# ASD2411.net
KiCad netlist of a schematic drawn in EAGLE
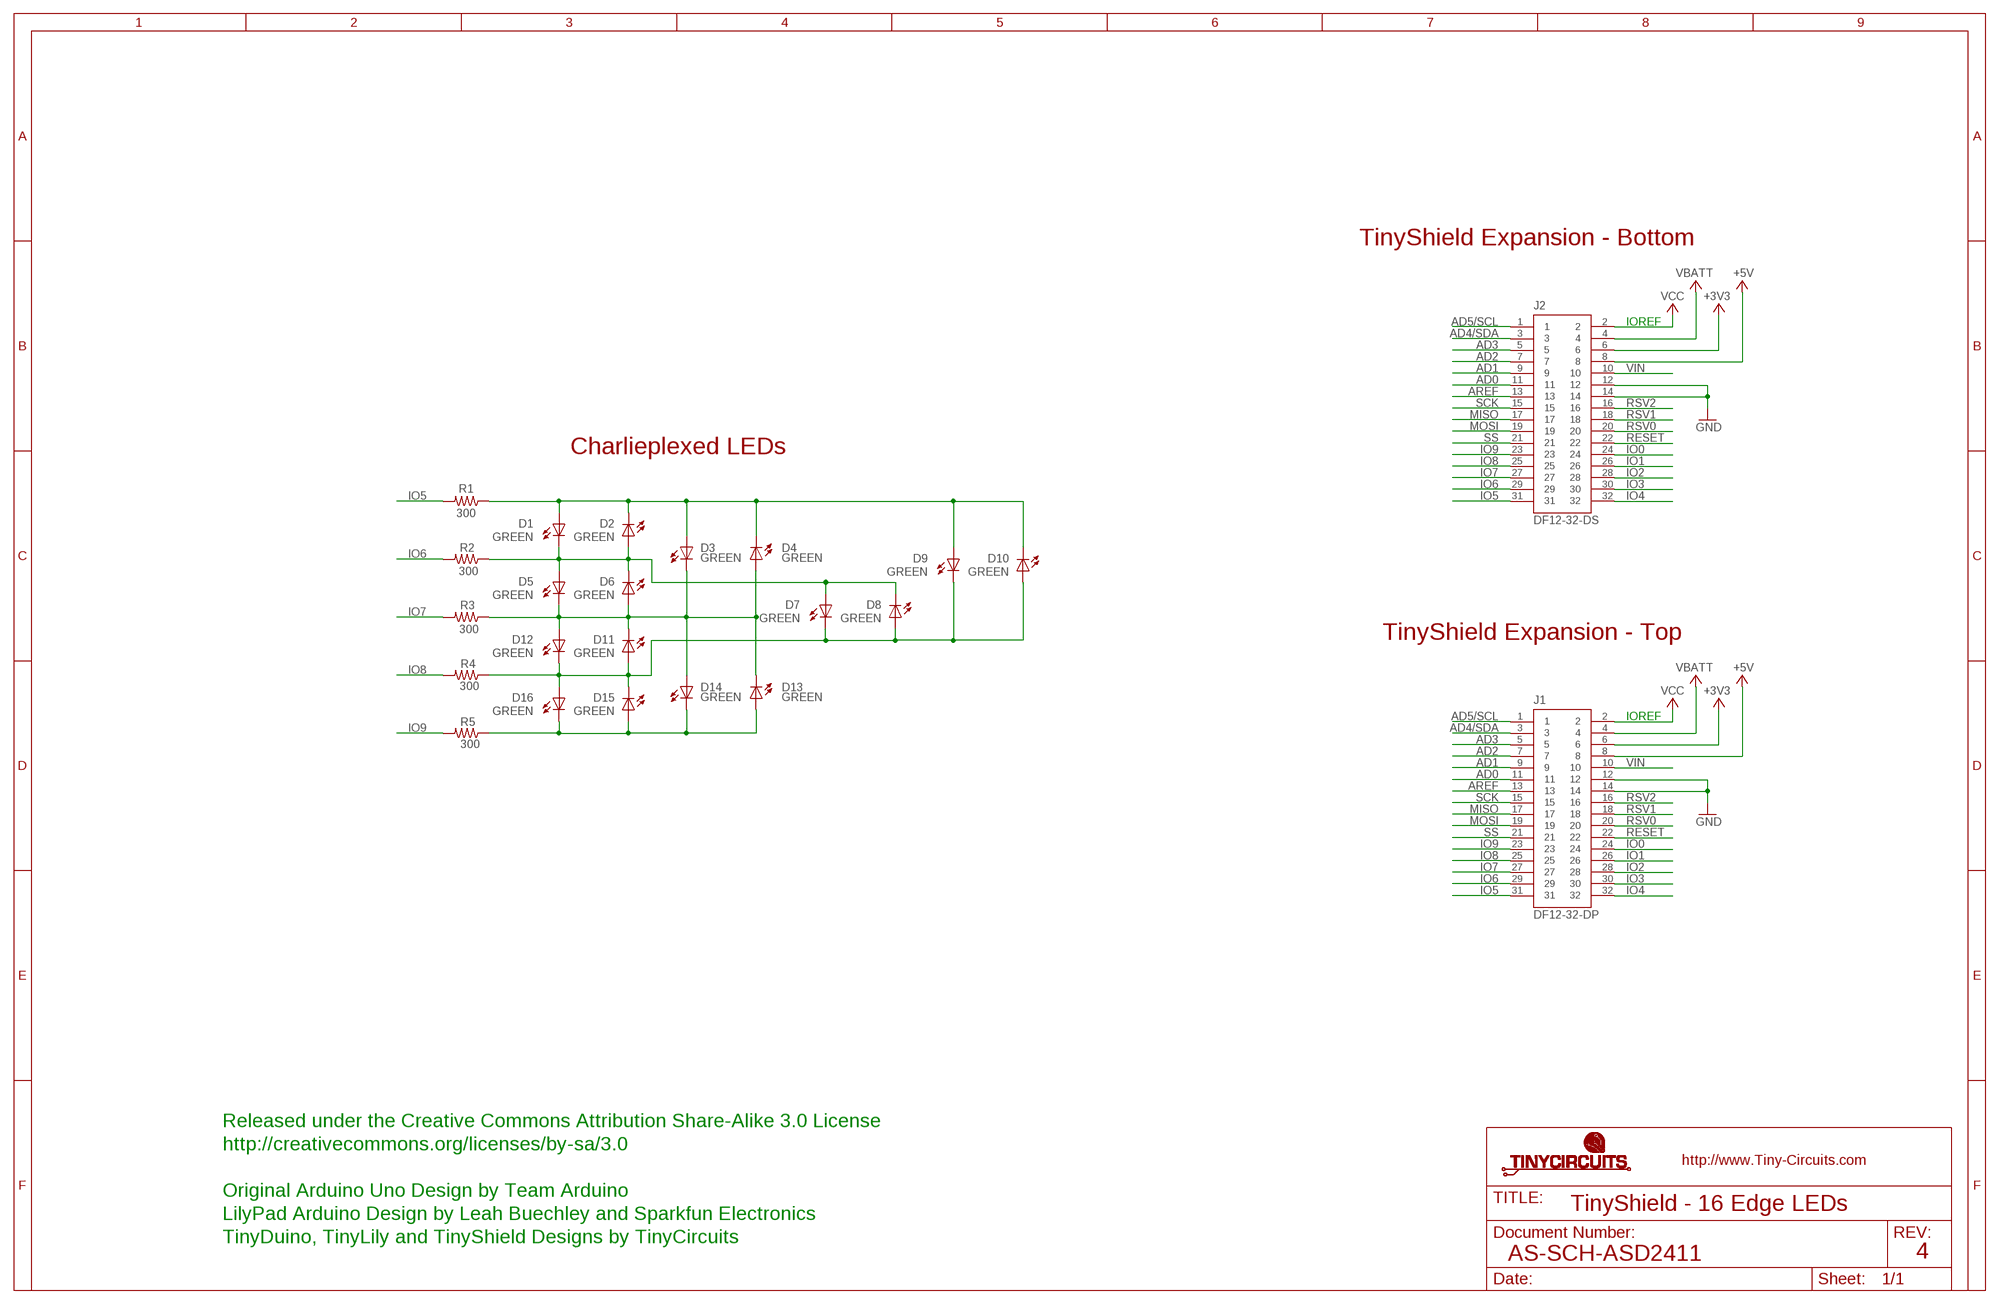
[diagram p0: schematic, sheet 1]

(export (version "E")
  (design (tool "Eeschema 10.0.6"))
  (components
    (comp (ref "D1")
      (value "GREEN")
      (footprint "eagle-import:LNJ_LED")
      (fields (field (name "PARTNO") "AS-ITM-00011") (field (name "PARTNO_1") "AS-ITM-00011"))
      (libsource (lib "eagle-import") (part "AS-ITM-00011"))
    )
    (comp (ref "D2")
      (value "GREEN")
      (footprint "eagle-import:LNJ_LED")
      (fields (field (name "PARTNO") "AS-ITM-00011") (field (name "PARTNO_1") "AS-ITM-00011"))
      (libsource (lib "eagle-import") (part "AS-ITM-00011"))
    )
    (comp (ref "D3")
      (value "GREEN")
      (footprint "eagle-import:LNJ_LED")
      (fields (field (name "PARTNO") "AS-ITM-00011") (field (name "PARTNO_1") "AS-ITM-00011"))
      (libsource (lib "eagle-import") (part "AS-ITM-00011"))
    )
    (comp (ref "D4")
      (value "GREEN")
      (footprint "eagle-import:LNJ_LED")
      (fields (field (name "PARTNO") "AS-ITM-00011") (field (name "PARTNO_1") "AS-ITM-00011"))
      (libsource (lib "eagle-import") (part "AS-ITM-00011"))
    )
    (comp (ref "D5")
      (value "GREEN")
      (footprint "eagle-import:LNJ_LED")
      (fields (field (name "PARTNO") "AS-ITM-00011") (field (name "PARTNO_1") "AS-ITM-00011"))
      (libsource (lib "eagle-import") (part "AS-ITM-00011"))
    )
    (comp (ref "D6")
      (value "GREEN")
      (footprint "eagle-import:LNJ_LED")
      (fields (field (name "PARTNO") "AS-ITM-00011") (field (name "PARTNO_1") "AS-ITM-00011"))
      (libsource (lib "eagle-import") (part "AS-ITM-00011"))
    )
    (comp (ref "D7")
      (value "GREEN")
      (footprint "eagle-import:LNJ_LED")
      (fields (field (name "PARTNO") "AS-ITM-00011") (field (name "PARTNO_1") "AS-ITM-00011"))
      (libsource (lib "eagle-import") (part "AS-ITM-00011"))
    )
    (comp (ref "D8")
      (value "GREEN")
      (footprint "eagle-import:LNJ_LED")
      (fields (field (name "PARTNO") "AS-ITM-00011") (field (name "PARTNO_1") "AS-ITM-00011"))
      (libsource (lib "eagle-import") (part "AS-ITM-00011"))
    )
    (comp (ref "D9")
      (value "GREEN")
      (footprint "eagle-import:LNJ_LED")
      (fields (field (name "PARTNO") "AS-ITM-00011") (field (name "PARTNO_1") "AS-ITM-00011"))
      (libsource (lib "eagle-import") (part "AS-ITM-00011"))
    )
    (comp (ref "D10")
      (value "GREEN")
      (footprint "eagle-import:LNJ_LED")
      (fields (field (name "PARTNO") "AS-ITM-00011") (field (name "PARTNO_1") "AS-ITM-00011"))
      (libsource (lib "eagle-import") (part "AS-ITM-00011"))
    )
    (comp (ref "D11")
      (value "GREEN")
      (footprint "eagle-import:LNJ_LED")
      (fields (field (name "PARTNO") "AS-ITM-00011") (field (name "PARTNO_1") "AS-ITM-00011"))
      (libsource (lib "eagle-import") (part "AS-ITM-00011"))
    )
    (comp (ref "D12")
      (value "GREEN")
      (footprint "eagle-import:LNJ_LED")
      (fields (field (name "PARTNO") "AS-ITM-00011") (field (name "PARTNO_1") "AS-ITM-00011"))
      (libsource (lib "eagle-import") (part "AS-ITM-00011"))
    )
    (comp (ref "D13")
      (value "GREEN")
      (footprint "eagle-import:LNJ_LED")
      (fields (field (name "PARTNO") "AS-ITM-00011") (field (name "PARTNO_1") "AS-ITM-00011"))
      (libsource (lib "eagle-import") (part "AS-ITM-00011"))
    )
    (comp (ref "D14")
      (value "GREEN")
      (footprint "eagle-import:LNJ_LED")
      (fields (field (name "PARTNO") "AS-ITM-00011") (field (name "PARTNO_1") "AS-ITM-00011"))
      (libsource (lib "eagle-import") (part "AS-ITM-00011"))
    )
    (comp (ref "D15")
      (value "GREEN")
      (footprint "eagle-import:LNJ_LED")
      (fields (field (name "PARTNO") "AS-ITM-00011") (field (name "PARTNO_1") "AS-ITM-00011"))
      (libsource (lib "eagle-import") (part "AS-ITM-00011"))
    )
    (comp (ref "D16")
      (value "GREEN")
      (footprint "eagle-import:LNJ_LED")
      (fields (field (name "PARTNO") "AS-ITM-00011") (field (name "PARTNO_1") "AS-ITM-00011"))
      (libsource (lib "eagle-import") (part "AS-ITM-00011"))
    )
    (comp (ref "J1")
      (value "DF12-32-DP")
      (footprint "eagle-import:DF12-32-DP")
      (fields (field (name "PARTNO") "AS-ITM-00015") (field (name "PARTNO_1") "AS-ITM-00015"))
      (libsource (lib "eagle-import") (part "AS-ITM-00015"))
    )
    (comp (ref "J2")
      (value "DF12-32-DS")
      (footprint "eagle-import:DF12-32-DS")
      (fields (field (name "PARTNO") "AS-ITM-00012") (field (name "PARTNO_1") "AS-ITM-00012"))
      (libsource (lib "eagle-import") (part "AS-ITM-00012"))
    )
    (comp (ref "R1")
      (value "300")
      (footprint "eagle-import:0402")
      (fields (field (name "PARTNO") "AS-ITM-00016") (field (name "PARTNO_1") "AS-ITM-00016"))
      (libsource (lib "eagle-import") (part "AS-ITM-00016"))
    )
    (comp (ref "R2")
      (value "300")
      (footprint "eagle-import:0402")
      (fields (field (name "PARTNO") "AS-ITM-00016"))
      (libsource (lib "eagle-import") (part "AS-ITM-00016"))
    )
    (comp (ref "R3")
      (value "300")
      (footprint "eagle-import:0402")
      (fields (field (name "PARTNO") "AS-ITM-00016"))
      (libsource (lib "eagle-import") (part "AS-ITM-00016"))
    )
    (comp (ref "R4")
      (value "300")
      (footprint "eagle-import:0402")
      (fields (field (name "PARTNO") "AS-ITM-00016"))
      (libsource (lib "eagle-import") (part "AS-ITM-00016"))
    )
    (comp (ref "R5")
      (value "300")
      (footprint "eagle-import:0402")
      (fields (field (name "PARTNO") "AS-ITM-00016"))
      (libsource (lib "eagle-import") (part "AS-ITM-00016"))
    )
  )
  (nets
    (net (code "1") (name "+3V3") (class "Default")
      (node (ref "J1") (pin "6") (pinfunction "6_6") (pintype "bidirectional"))
      (node (ref "J2") (pin "6") (pinfunction "6_6") (pintype "bidirectional"))
    )
    (net (code "2") (name "+5V") (class "Default")
      (node (ref "J1") (pin "8") (pinfunction "8_8") (pintype "bidirectional"))
      (node (ref "J2") (pin "8") (pinfunction "8_8") (pintype "bidirectional"))
    )
    (net (code "3") (name "/AD0") (class "Default")
      (node (ref "J1") (pin "11") (pinfunction "11_11") (pintype "bidirectional"))
      (node (ref "J2") (pin "11") (pinfunction "11_11") (pintype "bidirectional"))
    )
    (net (code "4") (name "/AD1") (class "Default")
      (node (ref "J1") (pin "9") (pinfunction "9_9") (pintype "bidirectional"))
      (node (ref "J2") (pin "9") (pinfunction "9_9") (pintype "bidirectional"))
    )
    (net (code "5") (name "/AD2") (class "Default")
      (node (ref "J1") (pin "7") (pinfunction "7_7") (pintype "bidirectional"))
      (node (ref "J2") (pin "7") (pinfunction "7_7") (pintype "bidirectional"))
    )
    (net (code "6") (name "/AD3") (class "Default")
      (node (ref "J1") (pin "5") (pinfunction "5_5") (pintype "bidirectional"))
      (node (ref "J2") (pin "5") (pinfunction "5_5") (pintype "bidirectional"))
    )
    (net (code "7") (name "/AD4{slash}SDA") (class "Default")
      (node (ref "J1") (pin "3") (pinfunction "3_3") (pintype "bidirectional"))
      (node (ref "J2") (pin "3") (pinfunction "3_3") (pintype "bidirectional"))
    )
    (net (code "8") (name "/AD5{slash}SCL") (class "Default")
      (node (ref "J1") (pin "1") (pinfunction "1_1") (pintype "bidirectional"))
      (node (ref "J2") (pin "1") (pinfunction "1_1") (pintype "bidirectional"))
    )
    (net (code "9") (name "/AREF") (class "Default")
      (node (ref "J1") (pin "13") (pinfunction "13_13") (pintype "bidirectional"))
      (node (ref "J2") (pin "13") (pinfunction "13_13") (pintype "bidirectional"))
    )
    (net (code "10") (name "/IO0") (class "Default")
      (node (ref "J1") (pin "24") (pinfunction "24_24") (pintype "bidirectional"))
      (node (ref "J2") (pin "24") (pinfunction "24_24") (pintype "bidirectional"))
    )
    (net (code "11") (name "/IO1") (class "Default")
      (node (ref "J1") (pin "26") (pinfunction "26_26") (pintype "bidirectional"))
      (node (ref "J2") (pin "26") (pinfunction "26_26") (pintype "bidirectional"))
    )
    (net (code "12") (name "/IO2") (class "Default")
      (node (ref "J1") (pin "28") (pinfunction "28_28") (pintype "bidirectional"))
      (node (ref "J2") (pin "28") (pinfunction "28_28") (pintype "bidirectional"))
    )
    (net (code "13") (name "/IO3") (class "Default")
      (node (ref "J1") (pin "30") (pinfunction "30_30") (pintype "bidirectional"))
      (node (ref "J2") (pin "30") (pinfunction "30_30") (pintype "bidirectional"))
    )
    (net (code "14") (name "/IO4") (class "Default")
      (node (ref "J1") (pin "32") (pinfunction "32_32") (pintype "bidirectional"))
      (node (ref "J2") (pin "32") (pinfunction "32_32") (pintype "bidirectional"))
    )
    (net (code "15") (name "/IO5") (class "Default")
      (node (ref "J1") (pin "31") (pinfunction "31_31") (pintype "bidirectional"))
      (node (ref "J2") (pin "31") (pinfunction "31_31") (pintype "bidirectional"))
      (node (ref "R1") (pin "2") (pinfunction "2_2") (pintype "passive"))
    )
    (net (code "16") (name "/IO6") (class "Default")
      (node (ref "J1") (pin "29") (pinfunction "29_29") (pintype "bidirectional"))
      (node (ref "J2") (pin "29") (pinfunction "29_29") (pintype "bidirectional"))
      (node (ref "R2") (pin "2") (pinfunction "2_2") (pintype "passive"))
    )
    (net (code "17") (name "/IO7") (class "Default")
      (node (ref "J1") (pin "27") (pinfunction "27_27") (pintype "bidirectional"))
      (node (ref "J2") (pin "27") (pinfunction "27_27") (pintype "bidirectional"))
      (node (ref "R3") (pin "2") (pinfunction "2_2") (pintype "passive"))
    )
    (net (code "18") (name "/IO8") (class "Default")
      (node (ref "J1") (pin "25") (pinfunction "25_25") (pintype "bidirectional"))
      (node (ref "J2") (pin "25") (pinfunction "25_25") (pintype "bidirectional"))
      (node (ref "R4") (pin "2") (pinfunction "2_2") (pintype "passive"))
    )
    (net (code "19") (name "/IO9") (class "Default")
      (node (ref "J1") (pin "23") (pinfunction "23_23") (pintype "bidirectional"))
      (node (ref "J2") (pin "23") (pinfunction "23_23") (pintype "bidirectional"))
      (node (ref "R5") (pin "2") (pinfunction "2_2") (pintype "passive"))
    )
    (net (code "20") (name "/MISO") (class "Default")
      (node (ref "J1") (pin "17") (pinfunction "17_17") (pintype "bidirectional"))
      (node (ref "J2") (pin "17") (pinfunction "17_17") (pintype "bidirectional"))
    )
    (net (code "21") (name "/MOSI") (class "Default")
      (node (ref "J1") (pin "19") (pinfunction "19_19") (pintype "bidirectional"))
      (node (ref "J2") (pin "19") (pinfunction "19_19") (pintype "bidirectional"))
    )
    (net (code "22") (name "/RESET") (class "Default")
      (node (ref "J1") (pin "22") (pinfunction "22_22") (pintype "bidirectional"))
      (node (ref "J2") (pin "22") (pinfunction "22_22") (pintype "bidirectional"))
    )
    (net (code "23") (name "/RSV0") (class "Default")
      (node (ref "J1") (pin "20") (pinfunction "20_20") (pintype "bidirectional"))
      (node (ref "J2") (pin "20") (pinfunction "20_20") (pintype "bidirectional"))
    )
    (net (code "24") (name "/RSV1") (class "Default")
      (node (ref "J1") (pin "18") (pinfunction "18_18") (pintype "bidirectional"))
      (node (ref "J2") (pin "18") (pinfunction "18_18") (pintype "bidirectional"))
    )
    (net (code "25") (name "/RSV2") (class "Default")
      (node (ref "J1") (pin "16") (pinfunction "16_16") (pintype "bidirectional"))
      (node (ref "J2") (pin "16") (pinfunction "16_16") (pintype "bidirectional"))
    )
    (net (code "26") (name "/SCK") (class "Default")
      (node (ref "J1") (pin "15") (pinfunction "15_15") (pintype "bidirectional"))
      (node (ref "J2") (pin "15") (pinfunction "15_15") (pintype "bidirectional"))
    )
    (net (code "27") (name "/SS") (class "Default")
      (node (ref "J1") (pin "21") (pinfunction "21_21") (pintype "bidirectional"))
      (node (ref "J2") (pin "21") (pinfunction "21_21") (pintype "bidirectional"))
    )
    (net (code "28") (name "/VIN") (class "Default")
      (node (ref "J1") (pin "10") (pinfunction "10_10") (pintype "bidirectional"))
      (node (ref "J2") (pin "10") (pinfunction "10_10") (pintype "bidirectional"))
    )
    (net (code "29") (name "GND") (class "Default")
      (node (ref "J1") (pin "12") (pinfunction "12_12") (pintype "bidirectional"))
      (node (ref "J1") (pin "14") (pinfunction "14_14") (pintype "bidirectional"))
      (node (ref "J2") (pin "12") (pinfunction "12_12") (pintype "bidirectional"))
      (node (ref "J2") (pin "14") (pinfunction "14_14") (pintype "bidirectional"))
    )
    (net (code "30") (name "Net-(D1-PadA)") (class "Default")
      (node (ref "D1") (pin "A") (pinfunction "A_A") (pintype "passive"))
      (node (ref "D10") (pin "C") (pinfunction "C_C") (pintype "passive"))
      (node (ref "D2") (pin "C") (pinfunction "C_C") (pintype "passive"))
      (node (ref "D3") (pin "A") (pinfunction "A_A") (pintype "passive"))
      (node (ref "D4") (pin "C") (pinfunction "C_C") (pintype "passive"))
      (node (ref "D9") (pin "A") (pinfunction "A_A") (pintype "passive"))
      (node (ref "R1") (pin "1") (pinfunction "1_1") (pintype "passive"))
    )
    (net (code "31") (name "Net-(D1-PadC)") (class "Default")
      (node (ref "D1") (pin "C") (pinfunction "C_C") (pintype "passive"))
      (node (ref "D2") (pin "A") (pinfunction "A_A") (pintype "passive"))
      (node (ref "D5") (pin "A") (pinfunction "A_A") (pintype "passive"))
      (node (ref "D6") (pin "C") (pinfunction "C_C") (pintype "passive"))
      (node (ref "D7") (pin "A") (pinfunction "A_A") (pintype "passive"))
      (node (ref "D8") (pin "C") (pinfunction "C_C") (pintype "passive"))
      (node (ref "R2") (pin "1") (pinfunction "1_1") (pintype "passive"))
    )
    (net (code "32") (name "Net-(D10-PadA)") (class "Default")
      (node (ref "D10") (pin "A") (pinfunction "A_A") (pintype "passive"))
      (node (ref "D11") (pin "A") (pinfunction "A_A") (pintype "passive"))
      (node (ref "D12") (pin "C") (pinfunction "C_C") (pintype "passive"))
      (node (ref "D15") (pin "C") (pinfunction "C_C") (pintype "passive"))
      (node (ref "D16") (pin "A") (pinfunction "A_A") (pintype "passive"))
      (node (ref "D7") (pin "C") (pinfunction "C_C") (pintype "passive"))
      (node (ref "D8") (pin "A") (pinfunction "A_A") (pintype "passive"))
      (node (ref "D9") (pin "C") (pinfunction "C_C") (pintype "passive"))
      (node (ref "R4") (pin "1") (pinfunction "1_1") (pintype "passive"))
    )
    (net (code "33") (name "Net-(D11-PadC)") (class "Default")
      (node (ref "D11") (pin "C") (pinfunction "C_C") (pintype "passive"))
      (node (ref "D12") (pin "A") (pinfunction "A_A") (pintype "passive"))
      (node (ref "D13") (pin "C") (pinfunction "C_C") (pintype "passive"))
      (node (ref "D14") (pin "A") (pinfunction "A_A") (pintype "passive"))
      (node (ref "D3") (pin "C") (pinfunction "C_C") (pintype "passive"))
      (node (ref "D4") (pin "A") (pinfunction "A_A") (pintype "passive"))
      (node (ref "D5") (pin "C") (pinfunction "C_C") (pintype "passive"))
      (node (ref "D6") (pin "A") (pinfunction "A_A") (pintype "passive"))
      (node (ref "R3") (pin "1") (pinfunction "1_1") (pintype "passive"))
    )
    (net (code "34") (name "Net-(D13-PadA)") (class "Default")
      (node (ref "D13") (pin "A") (pinfunction "A_A") (pintype "passive"))
      (node (ref "D14") (pin "C") (pinfunction "C_C") (pintype "passive"))
      (node (ref "D15") (pin "A") (pinfunction "A_A") (pintype "passive"))
      (node (ref "D16") (pin "C") (pinfunction "C_C") (pintype "passive"))
      (node (ref "R5") (pin "1") (pinfunction "1_1") (pintype "passive"))
    )
    (net (code "35") (name "VBATT") (class "Default")
      (node (ref "J1") (pin "4") (pinfunction "4_4") (pintype "bidirectional"))
      (node (ref "J2") (pin "4") (pinfunction "4_4") (pintype "bidirectional"))
    )
    (net (code "36") (name "VCC") (class "Default")
      (node (ref "J1") (pin "2") (pinfunction "2_2") (pintype "bidirectional"))
      (node (ref "J2") (pin "2") (pinfunction "2_2") (pintype "bidirectional"))
    )
  )
)
